# Option_Nand_Flash.net
KiCad netlist of a schematic drawn in Altium Designer
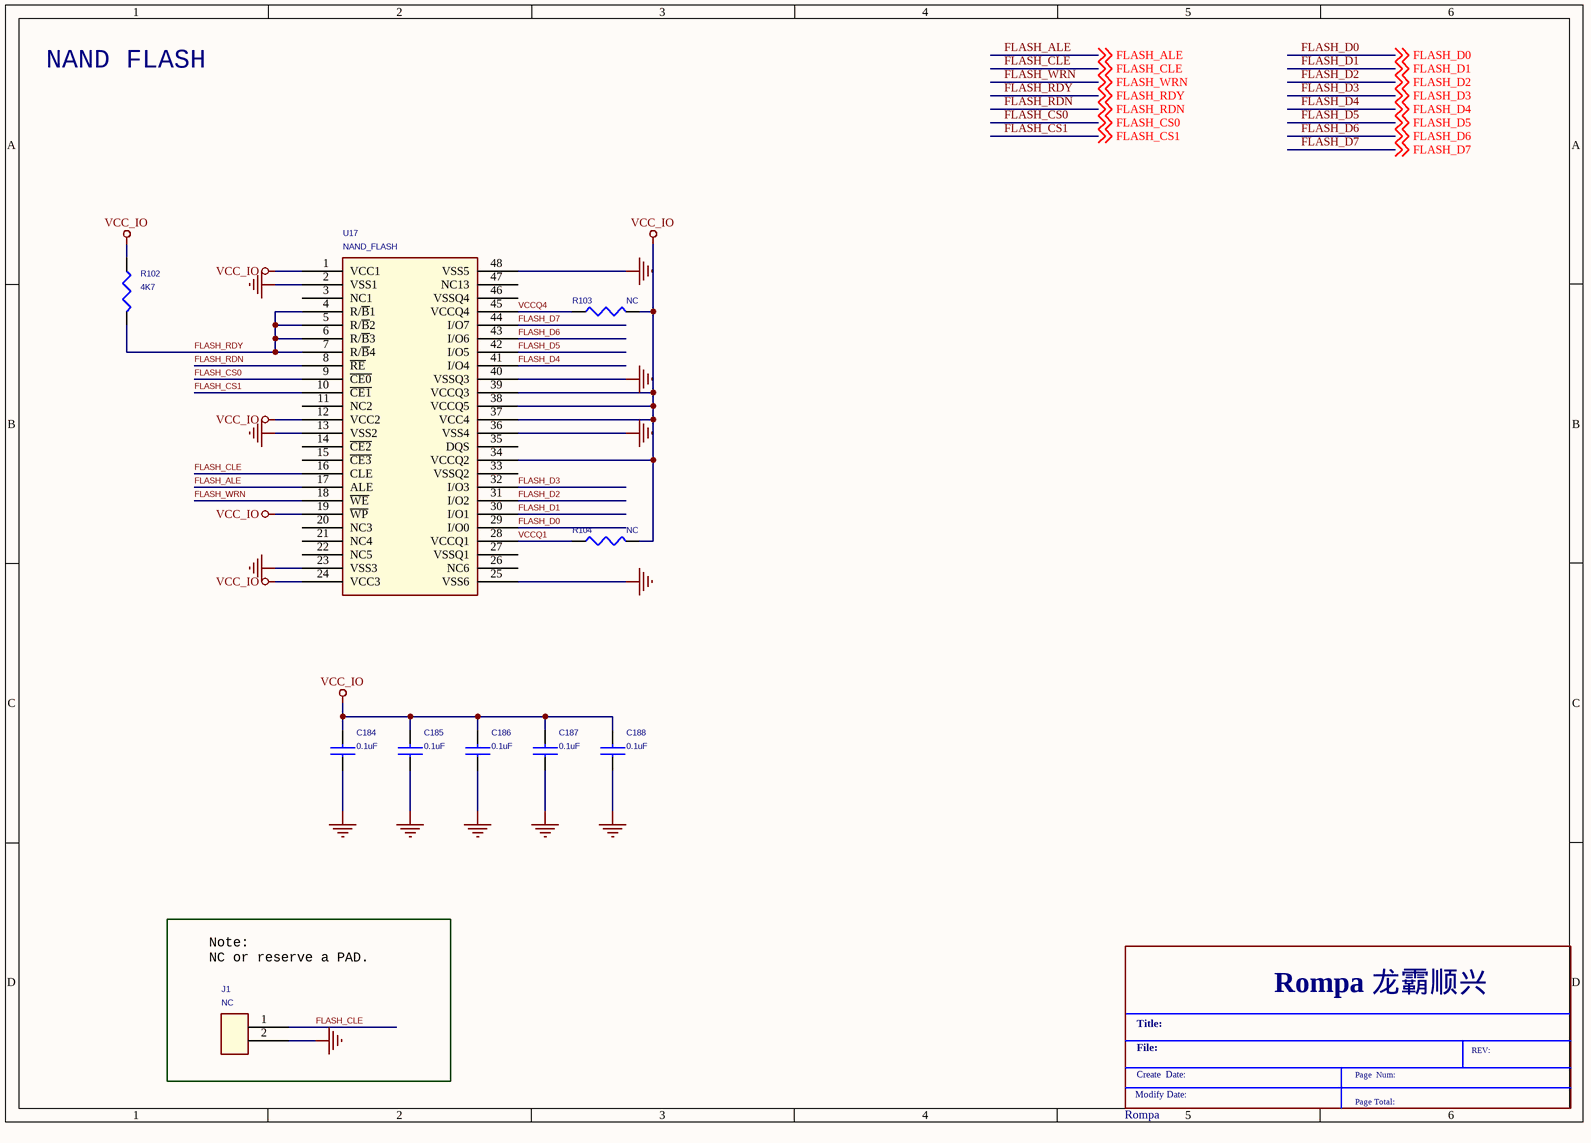
[diagram p0: Option_Nand_Flash.SchDoc]

(export (version "E")
  (design (tool "Eeschema 10.0.6"))
  (components
    (comp (ref "C184")
      (value "0.1uF")
      (footprint "C0402")
      (description "RoHS CHIP CAP 0.1uF +10/-10% X7R")
      (libsource (lib "*") (part "CAP NP"))
    )
    (comp (ref "C185")
      (value "0.1uF")
      (footprint "C0402")
      (description "RoHS CHIP CAP 0.1uF +10/-10% X7R")
      (libsource (lib "*") (part "CAP NP"))
    )
    (comp (ref "C186")
      (value "0.1uF")
      (footprint "C0402")
      (description "RoHS CHIP CAP 0.1uF +10/-10% X7R")
      (libsource (lib "*") (part "CAP NP"))
    )
    (comp (ref "C187")
      (value "0.1uF")
      (footprint "C0402")
      (description "RoHS CHIP CAP 0.1uF +10/-10% X7R")
      (libsource (lib "*") (part "CAP NP"))
    )
    (comp (ref "C188")
      (value "0.1uF")
      (footprint "C0402")
      (description "RoHS CHIP CAP 0.1uF +10/-10% X7R")
      (libsource (lib "*") (part "CAP NP"))
    )
    (comp (ref "J1")
      (value "NC")
      (footprint "R0603")
      (description "TEST")
      (libsource (lib "*") (part "CON2"))
    )
    (comp (ref "R102")
      (value "4K7")
      (footprint "R0402")
      (description "ROHS CHIP RES 4.7K 1/16W 5%")
      (libsource (lib "*") (part "RES 1B"))
    )
    (comp (ref "R103")
      (value "NC")
      (footprint "R0402")
      (description "ROHS CHIP RES 4.7K 1/16W 5%")
      (libsource (lib "*") (part "RES 1B"))
    )
    (comp (ref "R104")
      (value "NC")
      (footprint "R0402")
      (description "ROHS CHIP RES 4.7K 1/16W 5%")
      (libsource (lib "*") (part "RES 1B"))
    )
    (comp (ref "U17")
      (value "NAND_FLASH")
      (footprint "TSOP1-48")
      (description "NAND Flash,2.7V,3.3V,3.6V,2G*8,N/A,-40℃~85℃,TSOP-48P")
      (libsource (lib "*") (part "NANDFLASH_0"))
    )
  )
  (nets
    (net (code "1") (name "/VCCQ1") (class "Default")
      (node (ref "R104") (pin "1") (pinfunction "1_1") (pintype "passive"))
      (node (ref "U17") (pin "28") (pinfunction "VCCQ1_28") (pintype "passive"))
    )
    (net (code "2") (name "/VCCQ4") (class "Default")
      (node (ref "R103") (pin "1") (pinfunction "1_1") (pintype "passive"))
      (node (ref "U17") (pin "45") (pinfunction "VCCQ4_45") (pintype "passive"))
    )
    (net (code "3") (name "FLASH_ALE") (class "Default")
      (node (ref "U17") (pin "17") (pinfunction "ALE_17") (pintype "passive"))
    )
    (net (code "4") (name "FLASH_CLE") (class "Default")
      (node (ref "J1") (pin "1") (pinfunction "1_1") (pintype "passive"))
      (node (ref "U17") (pin "16") (pinfunction "CLE_16") (pintype "passive"))
    )
    (net (code "5") (name "FLASH_CS0") (class "Default")
      (node (ref "U17") (pin "9") (pinfunction "~{CE0}_9") (pintype "passive"))
    )
    (net (code "6") (name "FLASH_CS1") (class "Default")
      (node (ref "U17") (pin "10") (pinfunction "~{CE1}_10") (pintype "passive"))
    )
    (net (code "7") (name "FLASH_D0") (class "Default")
      (node (ref "U17") (pin "29") (pinfunction "I/O0_29") (pintype "passive"))
    )
    (net (code "8") (name "FLASH_D1") (class "Default")
      (node (ref "U17") (pin "30") (pinfunction "I/O1_30") (pintype "passive"))
    )
    (net (code "9") (name "FLASH_D2") (class "Default")
      (node (ref "U17") (pin "31") (pinfunction "I/O2_31") (pintype "passive"))
    )
    (net (code "10") (name "FLASH_D3") (class "Default")
      (node (ref "U17") (pin "32") (pinfunction "I/O3_32") (pintype "passive"))
    )
    (net (code "11") (name "FLASH_D4") (class "Default")
      (node (ref "U17") (pin "41") (pinfunction "I/O4_41") (pintype "passive"))
    )
    (net (code "12") (name "FLASH_D5") (class "Default")
      (node (ref "U17") (pin "42") (pinfunction "I/O5_42") (pintype "passive"))
    )
    (net (code "13") (name "FLASH_D6") (class "Default")
      (node (ref "U17") (pin "43") (pinfunction "I/O6_43") (pintype "passive"))
    )
    (net (code "14") (name "FLASH_D7") (class "Default")
      (node (ref "U17") (pin "44") (pinfunction "I/O7_44") (pintype "passive"))
    )
    (net (code "15") (name "FLASH_RDN") (class "Default")
      (node (ref "U17") (pin "8") (pinfunction "~{RE}_8") (pintype "passive"))
    )
    (net (code "16") (name "FLASH_RDY") (class "Default")
      (node (ref "R102") (pin "2") (pinfunction "2_2") (pintype "passive"))
      (node (ref "U17") (pin "4") (pinfunction "R/~{B}1_4") (pintype "passive"))
      (node (ref "U17") (pin "5") (pinfunction "R/~{B}2_5") (pintype "passive"))
      (node (ref "U17") (pin "6") (pinfunction "R/~{B}3_6") (pintype "passive"))
      (node (ref "U17") (pin "7") (pinfunction "R/~{B}4_7") (pintype "passive"))
    )
    (net (code "17") (name "FLASH_WRN") (class "Default")
      (node (ref "U17") (pin "18") (pinfunction "~{WE}_18") (pintype "passive"))
    )
    (net (code "18") (name "GND") (class "Default")
      (node (ref "C184") (pin "1") (pinfunction "1_1") (pintype "passive"))
      (node (ref "C185") (pin "1") (pinfunction "1_1") (pintype "passive"))
      (node (ref "C186") (pin "1") (pinfunction "1_1") (pintype "passive"))
      (node (ref "C187") (pin "1") (pinfunction "1_1") (pintype "passive"))
      (node (ref "C188") (pin "1") (pinfunction "1_1") (pintype "passive"))
      (node (ref "J1") (pin "2") (pinfunction "2_2") (pintype "passive"))
      (node (ref "U17") (pin "13") (pinfunction "VSS2_13") (pintype "power_in"))
      (node (ref "U17") (pin "2") (pinfunction "VSS1_2") (pintype "power_in"))
      (node (ref "U17") (pin "23") (pinfunction "VSS3_23") (pintype "power_in"))
      (node (ref "U17") (pin "25") (pinfunction "VSS6_25") (pintype "power_in"))
      (node (ref "U17") (pin "36") (pinfunction "VSS4_36") (pintype "power_in"))
      (node (ref "U17") (pin "40") (pinfunction "VSSQ3_40") (pintype "passive"))
      (node (ref "U17") (pin "48") (pinfunction "VSS5_48") (pintype "power_in"))
    )
    (net (code "19") (name "VCC_IO") (class "Default")
      (node (ref "C184") (pin "2") (pinfunction "2_2") (pintype "passive"))
      (node (ref "C185") (pin "2") (pinfunction "2_2") (pintype "passive"))
      (node (ref "C186") (pin "2") (pinfunction "2_2") (pintype "passive"))
      (node (ref "C187") (pin "2") (pinfunction "2_2") (pintype "passive"))
      (node (ref "C188") (pin "2") (pinfunction "2_2") (pintype "passive"))
      (node (ref "R102") (pin "1") (pinfunction "1_1") (pintype "passive"))
      (node (ref "R103") (pin "2") (pinfunction "2_2") (pintype "passive"))
      (node (ref "R104") (pin "2") (pinfunction "2_2") (pintype "passive"))
      (node (ref "U17") (pin "1") (pinfunction "VCC1_1") (pintype "power_in"))
      (node (ref "U17") (pin "12") (pinfunction "VCC2_12") (pintype "power_in"))
      (node (ref "U17") (pin "19") (pinfunction "~{WP}_19") (pintype "passive"))
      (node (ref "U17") (pin "24") (pinfunction "VCC3_24") (pintype "power_in"))
      (node (ref "U17") (pin "34") (pinfunction "VCCQ2_34") (pintype "power_in"))
      (node (ref "U17") (pin "37") (pinfunction "VCC4_37") (pintype "power_in"))
      (node (ref "U17") (pin "38") (pinfunction "VCCQ5_38") (pintype "power_in"))
      (node (ref "U17") (pin "39") (pinfunction "VCCQ3_39") (pintype "power_in"))
    )
    (net (code "20") (name "unconnected-(U17-DQS-Pad35)") (class "Default")
      (node (ref "U17") (pin "35") (pinfunction "DQS_35") (pintype "passive"))
    )
    (net (code "21") (name "unconnected-(U17-NC1-Pad3)") (class "Default")
      (node (ref "U17") (pin "3") (pinfunction "NC1_3") (pintype "passive"))
    )
    (net (code "22") (name "unconnected-(U17-NC2-Pad11)") (class "Default")
      (node (ref "U17") (pin "11") (pinfunction "NC2_11") (pintype "passive"))
    )
    (net (code "23") (name "unconnected-(U17-NC3-Pad20)") (class "Default")
      (node (ref "U17") (pin "20") (pinfunction "NC3_20") (pintype "passive"))
    )
    (net (code "24") (name "unconnected-(U17-NC4-Pad21)") (class "Default")
      (node (ref "U17") (pin "21") (pinfunction "NC4_21") (pintype "passive"))
    )
    (net (code "25") (name "unconnected-(U17-NC5-Pad22)") (class "Default")
      (node (ref "U17") (pin "22") (pinfunction "NC5_22") (pintype "passive"))
    )
    (net (code "26") (name "unconnected-(U17-NC6-Pad26)") (class "Default")
      (node (ref "U17") (pin "26") (pinfunction "NC6_26") (pintype "passive"))
    )
    (net (code "27") (name "unconnected-(U17-NC13-Pad47)") (class "Default")
      (node (ref "U17") (pin "47") (pinfunction "NC13_47") (pintype "passive"))
    )
    (net (code "28") (name "unconnected-(U17-VSSQ1-Pad27)") (class "Default")
      (node (ref "U17") (pin "27") (pinfunction "VSSQ1_27") (pintype "passive"))
    )
    (net (code "29") (name "unconnected-(U17-VSSQ2-Pad33)") (class "Default")
      (node (ref "U17") (pin "33") (pinfunction "VSSQ2_33") (pintype "passive"))
    )
    (net (code "30") (name "unconnected-(U17-VSSQ4-Pad46)") (class "Default")
      (node (ref "U17") (pin "46") (pinfunction "VSSQ4_46") (pintype "passive"))
    )
    (net (code "31") (name "unconnected-(U17-~{CE2}-Pad14)") (class "Default")
      (node (ref "U17") (pin "14") (pinfunction "~{CE2}_14") (pintype "passive"))
    )
    (net (code "32") (name "unconnected-(U17-~{CE3}-Pad15)") (class "Default")
      (node (ref "U17") (pin "15") (pinfunction "~{CE3}_15") (pintype "passive"))
    )
  )
)
